# familamp.net
KiCad netlist of a schematic drawn in EAGLE
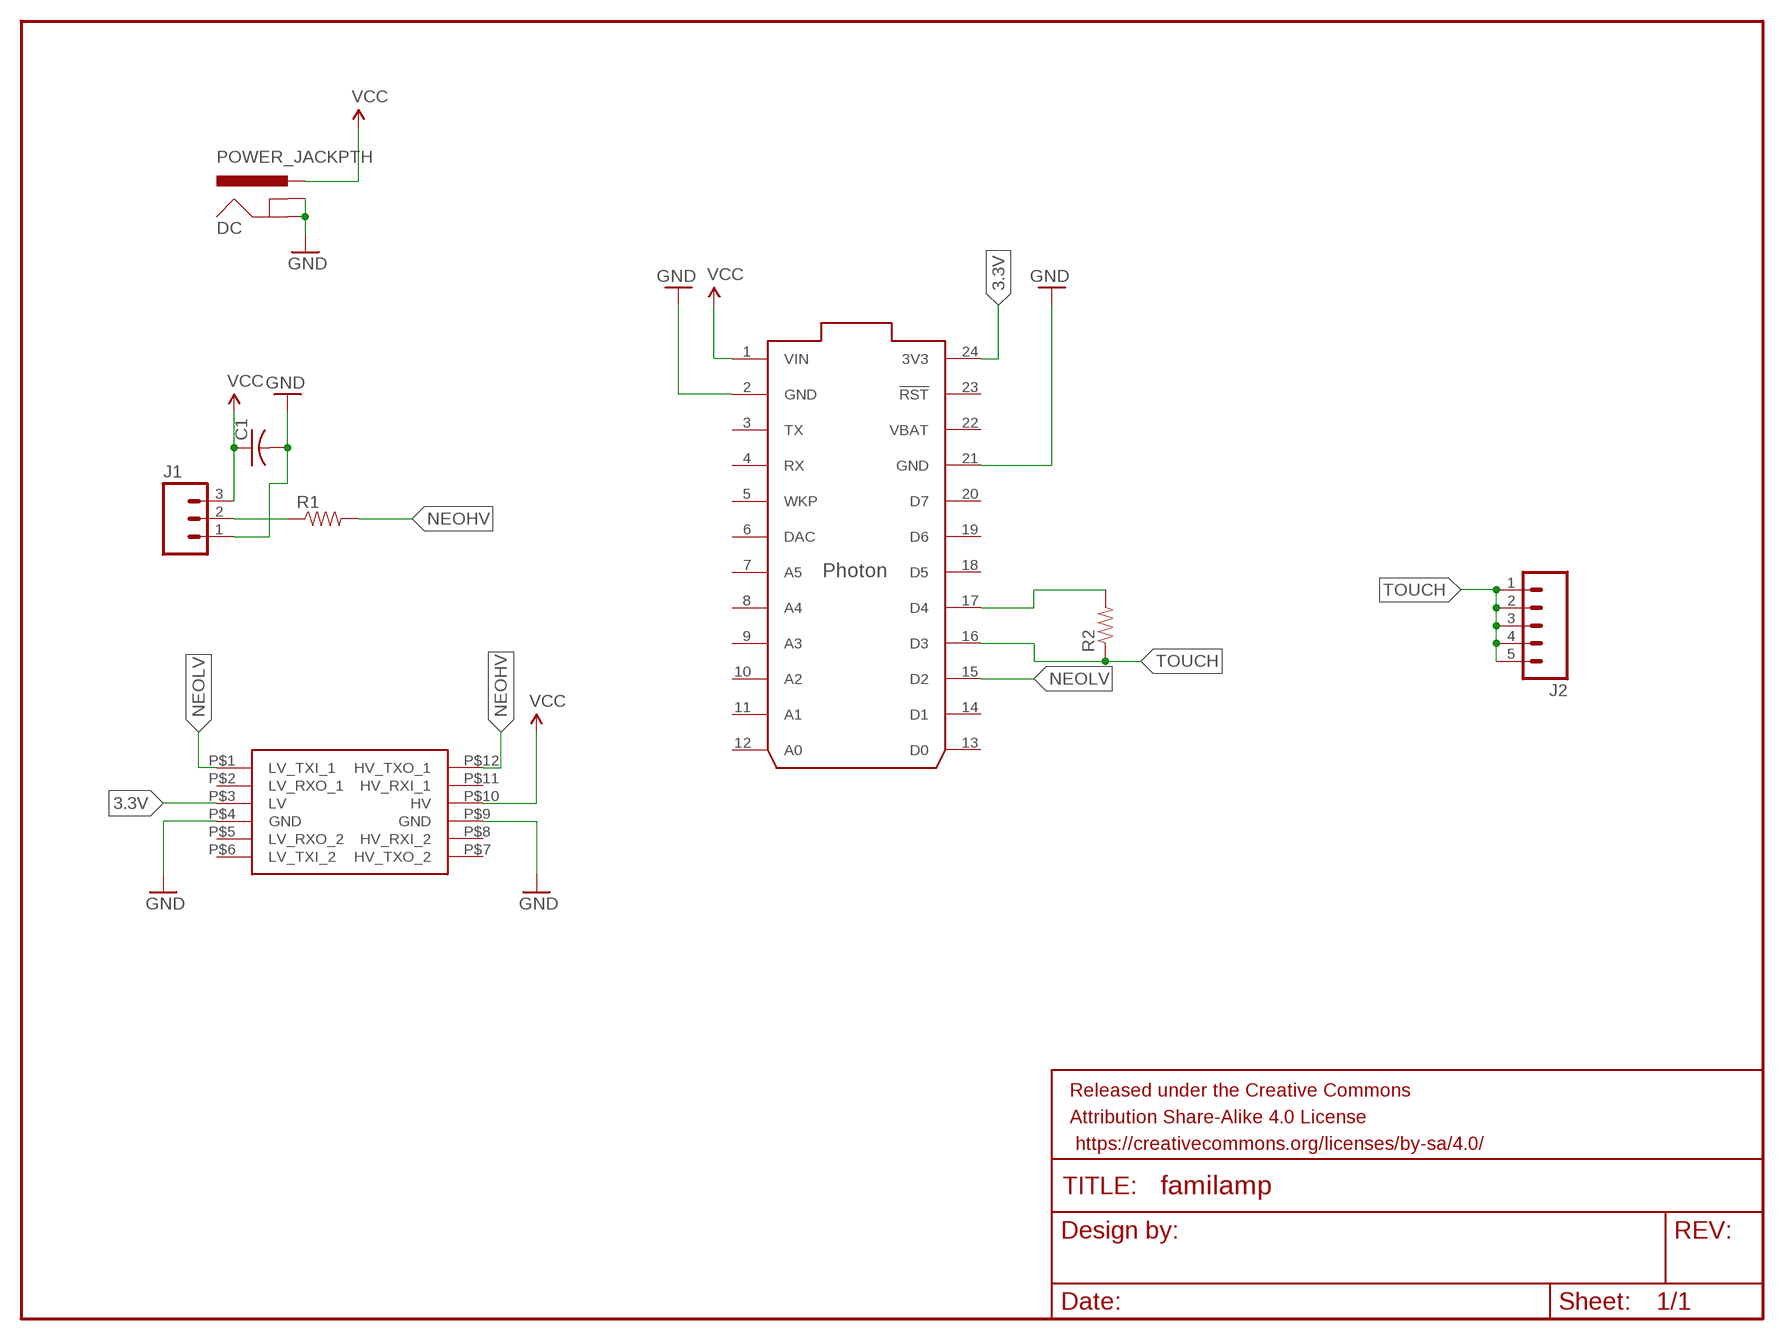
[diagram p0: schematic, sheet 1]

(export (version "E")
  (design (tool "Eeschema 10.0.6"))
  (components
    (comp (ref "C1")
      (value "C-US050-035X075")
      (footprint "eagle-import:C050-035X075")
      (libsource (lib "eagle-import") (part "C-US050-035X075"))
    )
    (comp (ref "DC")
      (value "POWER_JACKPTH")
      (footprint "eagle-import:POWER_JACK_PTH")
      (libsource (lib "eagle-import") (part "POWER_JACKPTH"))
    )
    (comp (ref "FRAME1")
      (value "FRAME-LETTER")
      (footprint "eagle-import:CREATIVE_COMMONS")
      (libsource (lib "eagle-import") (part "FRAME-LETTER"))
    )
    (comp (ref "J1")
      (value "M03PTH")
      (footprint "eagle-import:1X03")
      (libsource (lib "eagle-import") (part "M03PTH"))
    )
    (comp (ref "J2")
      (value "M05PTH")
      (footprint "eagle-import:1X05")
      (libsource (lib "eagle-import") (part "M05PTH"))
    )
    (comp (ref "PHOTON")
      (value "PHOTON_WITH_HEADERS")
      (footprint "eagle-import:PHOTON")
      (libsource (lib "eagle-import") (part "PHOTON_WITH_HEADERS"))
    )
    (comp (ref "R1")
      (value "RESISTORPTH-1/4W")
      (footprint "eagle-import:AXIAL-0.4")
      (libsource (lib "eagle-import") (part "RESISTORPTH-1/4W"))
    )
    (comp (ref "R2")
      (value "RESISTORPTH-1/4W")
      (footprint "eagle-import:AXIAL-0.4")
      (libsource (lib "eagle-import") (part "SparkFun-Resistors_RESISTORPTH-1/4W"))
    )
    (comp (ref "U$2")
      (value "LOGIC_LEVEL_CONVERTER")
      (footprint "eagle-import:LOGIC_LEVEL_CONVERTER")
      (libsource (lib "eagle-import") (part "LOGIC_LEVEL_CONVERTER"))
    )
  )
  (nets
    (net (code "1") (name "/VBAT") (class "Default")
      (node (ref "PHOTON") (pin "22") (pinfunction "VBAT_22") (pintype "power_in"))
    )
    (net (code "2") (name "3.3V") (class "Default")
      (node (ref "PHOTON") (pin "24") (pinfunction "3V3_24") (pintype "power_in"))
      (node (ref "U$2") (pin "P$3") (pinfunction "LV_P$3") (pintype "bidirectional"))
    )
    (net (code "3") (name "GND") (class "Default")
      (node (ref "C1") (pin "2") (pinfunction "2_2") (pintype "passive"))
      (node (ref "DC") (pin "GND") (pinfunction "GND_GND") (pintype "bidirectional"))
      (node (ref "DC") (pin "GNDBREAK") (pinfunction "GNDBREAK_GNDBREAK") (pintype "bidirectional"))
      (node (ref "J1") (pin "1") (pinfunction "1_1") (pintype "passive"))
      (node (ref "PHOTON") (pin "2") (pinfunction "GND_2") (pintype "power_in"))
      (node (ref "PHOTON") (pin "21") (pinfunction "GND_21") (pintype "power_in"))
      (node (ref "U$2") (pin "P$4") (pinfunction "GND_P$4") (pintype "bidirectional"))
      (node (ref "U$2") (pin "P$9") (pinfunction "GND_P$9") (pintype "bidirectional"))
    )
    (net (code "4") (name "NEOHV") (class "Default")
      (node (ref "R1") (pin "P$2") (pinfunction "2_P$2") (pintype "passive"))
      (node (ref "U$2") (pin "P$12") (pinfunction "HV_TXO_1_P$12") (pintype "bidirectional"))
    )
    (net (code "5") (name "NEOLV") (class "Default")
      (node (ref "PHOTON") (pin "15") (pinfunction "D2_15") (pintype "bidirectional"))
      (node (ref "U$2") (pin "P$1") (pinfunction "LV_TXI_1_P$1") (pintype "bidirectional"))
    )
    (net (code "6") (name "Net-(PHOTON-D4)") (class "Default")
      (node (ref "PHOTON") (pin "17") (pinfunction "D4_17") (pintype "bidirectional"))
      (node (ref "R2") (pin "P$2") (pinfunction "2_P$2") (pintype "passive"))
    )
    (net (code "7") (name "Net-(R1-1)") (class "Default")
      (node (ref "J1") (pin "2") (pinfunction "2_2") (pintype "passive"))
      (node (ref "R1") (pin "P$1") (pinfunction "1_P$1") (pintype "passive"))
    )
    (net (code "8") (name "TOUCH") (class "Default")
      (node (ref "J2") (pin "1") (pinfunction "1_1") (pintype "passive"))
      (node (ref "J2") (pin "2") (pinfunction "2_2") (pintype "passive"))
      (node (ref "J2") (pin "3") (pinfunction "3_3") (pintype "passive"))
      (node (ref "J2") (pin "4") (pinfunction "4_4") (pintype "passive"))
      (node (ref "J2") (pin "5") (pinfunction "5_5") (pintype "passive"))
      (node (ref "PHOTON") (pin "16") (pinfunction "D3_16") (pintype "bidirectional"))
      (node (ref "R2") (pin "P$1") (pinfunction "1_P$1") (pintype "passive"))
    )
    (net (code "9") (name "VCC") (class "Default")
      (node (ref "C1") (pin "1") (pinfunction "1_1") (pintype "passive"))
      (node (ref "DC") (pin "PWR") (pinfunction "PWR_PWR") (pintype "bidirectional"))
      (node (ref "J1") (pin "3") (pinfunction "3_3") (pintype "passive"))
      (node (ref "PHOTON") (pin "1") (pinfunction "VIN_1") (pintype "power_in"))
      (node (ref "U$2") (pin "P$10") (pinfunction "HV_P$10") (pintype "bidirectional"))
    )
    (net (code "10") (name "unconnected-(PHOTON-A0-Pad12)") (class "Default")
      (node (ref "PHOTON") (pin "12") (pinfunction "A0_12") (pintype "bidirectional"))
    )
    (net (code "11") (name "unconnected-(PHOTON-A1-Pad11)") (class "Default")
      (node (ref "PHOTON") (pin "11") (pinfunction "A1_11") (pintype "bidirectional"))
    )
    (net (code "12") (name "unconnected-(PHOTON-A2-Pad10)") (class "Default")
      (node (ref "PHOTON") (pin "10") (pinfunction "A2_10") (pintype "bidirectional"))
    )
    (net (code "13") (name "unconnected-(PHOTON-A3-Pad9)") (class "Default")
      (node (ref "PHOTON") (pin "9") (pinfunction "A3_9") (pintype "bidirectional"))
    )
    (net (code "14") (name "unconnected-(PHOTON-A4-Pad8)") (class "Default")
      (node (ref "PHOTON") (pin "8") (pinfunction "A4_8") (pintype "bidirectional"))
    )
    (net (code "15") (name "unconnected-(PHOTON-A5-Pad7)") (class "Default")
      (node (ref "PHOTON") (pin "7") (pinfunction "A5_7") (pintype "bidirectional"))
    )
    (net (code "16") (name "unconnected-(PHOTON-D0-Pad13)") (class "Default")
      (node (ref "PHOTON") (pin "13") (pinfunction "D0_13") (pintype "bidirectional"))
    )
    (net (code "17") (name "unconnected-(PHOTON-D1-Pad14)") (class "Default")
      (node (ref "PHOTON") (pin "14") (pinfunction "D1_14") (pintype "bidirectional"))
    )
    (net (code "18") (name "unconnected-(PHOTON-D5-Pad18)") (class "Default")
      (node (ref "PHOTON") (pin "18") (pinfunction "D5_18") (pintype "bidirectional"))
    )
    (net (code "19") (name "unconnected-(PHOTON-D6-Pad19)") (class "Default")
      (node (ref "PHOTON") (pin "19") (pinfunction "D6_19") (pintype "bidirectional"))
    )
    (net (code "20") (name "unconnected-(PHOTON-D7-Pad20)") (class "Default")
      (node (ref "PHOTON") (pin "20") (pinfunction "D7_20") (pintype "bidirectional"))
    )
    (net (code "21") (name "unconnected-(PHOTON-DAC-Pad6)") (class "Default")
      (node (ref "PHOTON") (pin "6") (pinfunction "DAC_6") (pintype "bidirectional"))
    )
    (net (code "22") (name "unconnected-(PHOTON-RX-Pad4)") (class "Default")
      (node (ref "PHOTON") (pin "4") (pinfunction "RX_4") (pintype "bidirectional"))
    )
    (net (code "23") (name "unconnected-(PHOTON-TX-Pad3)") (class "Default")
      (node (ref "PHOTON") (pin "3") (pinfunction "TX_3") (pintype "bidirectional"))
    )
    (net (code "24") (name "unconnected-(PHOTON-WKP-Pad5)") (class "Default")
      (node (ref "PHOTON") (pin "5") (pinfunction "WKP_5") (pintype "bidirectional"))
    )
    (net (code "25") (name "unconnected-(PHOTON-~{RST}-Pad23)") (class "Default")
      (node (ref "PHOTON") (pin "23") (pinfunction "~{RST}_23") (pintype "bidirectional"))
    )
    (net (code "26") (name "unconnected-(U$2-HV_RXI_1-PadP$11)") (class "Default")
      (node (ref "U$2") (pin "P$11") (pinfunction "HV_RXI_1_P$11") (pintype "bidirectional"))
    )
    (net (code "27") (name "unconnected-(U$2-HV_RXI_2-PadP$8)") (class "Default")
      (node (ref "U$2") (pin "P$8") (pinfunction "HV_RXI_2_P$8") (pintype "bidirectional"))
    )
    (net (code "28") (name "unconnected-(U$2-HV_TXO_2-PadP$7)") (class "Default")
      (node (ref "U$2") (pin "P$7") (pinfunction "HV_TXO_2_P$7") (pintype "bidirectional"))
    )
    (net (code "29") (name "unconnected-(U$2-LV_RXO_1-PadP$2)") (class "Default")
      (node (ref "U$2") (pin "P$2") (pinfunction "LV_RXO_1_P$2") (pintype "bidirectional"))
    )
    (net (code "30") (name "unconnected-(U$2-LV_RXO_2-PadP$5)") (class "Default")
      (node (ref "U$2") (pin "P$5") (pinfunction "LV_RXO_2_P$5") (pintype "bidirectional"))
    )
    (net (code "31") (name "unconnected-(U$2-LV_TXI_2-PadP$6)") (class "Default")
      (node (ref "U$2") (pin "P$6") (pinfunction "LV_TXI_2_P$6") (pintype "bidirectional"))
    )
  )
)
